# untitled.net
KiCad netlist of a schematic drawn in EAGLE
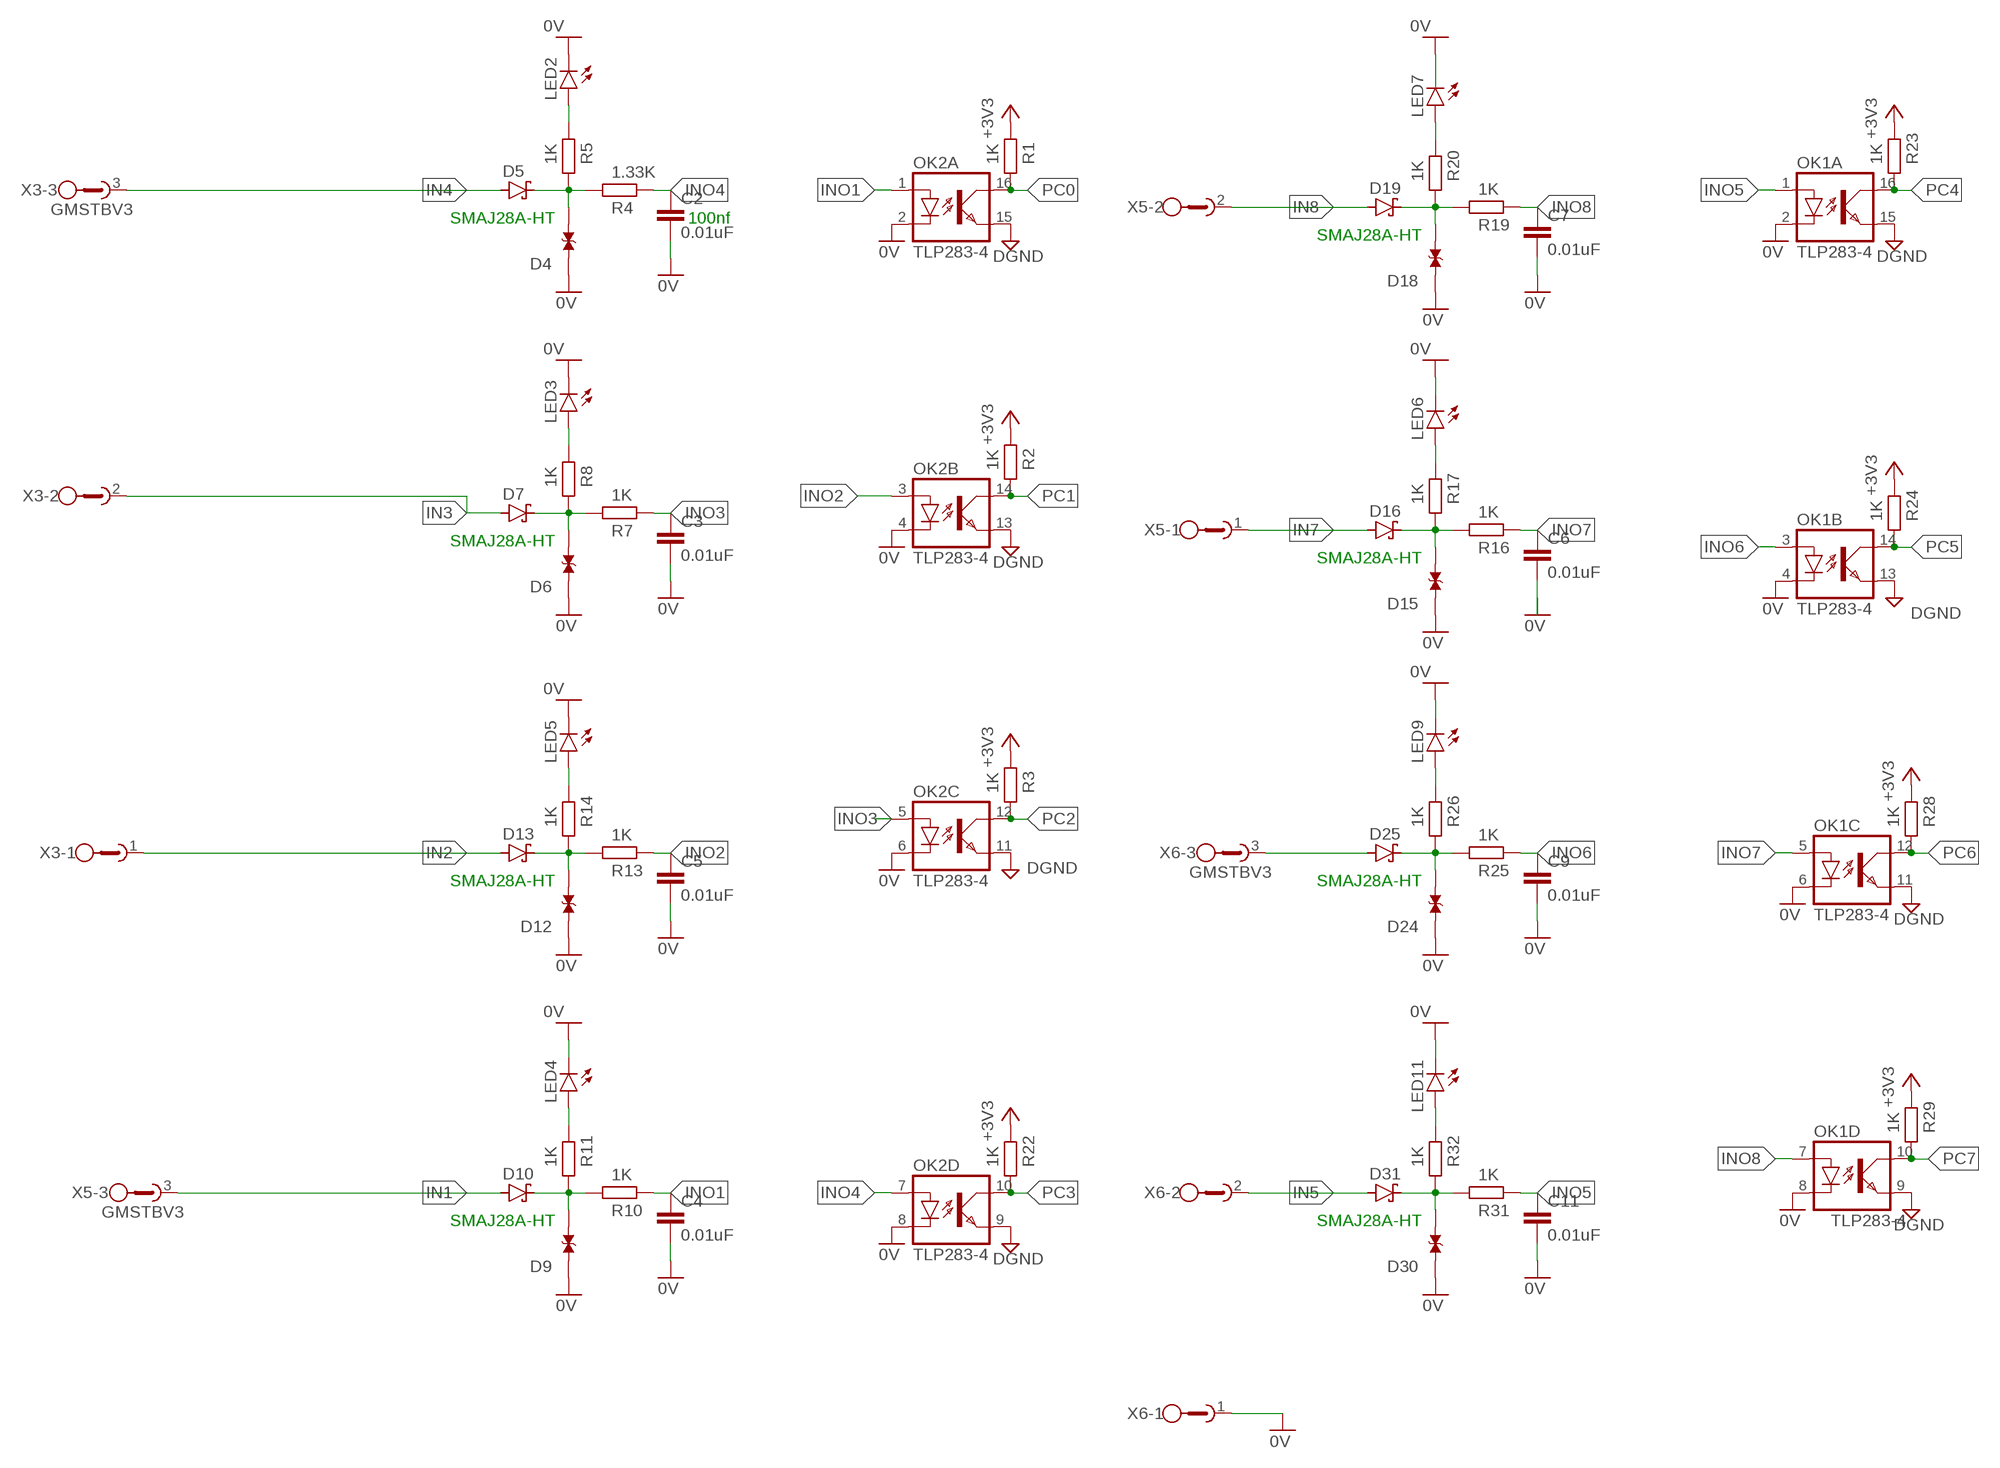
[diagram p0: schematic, sheet 1, part 1 of 2]
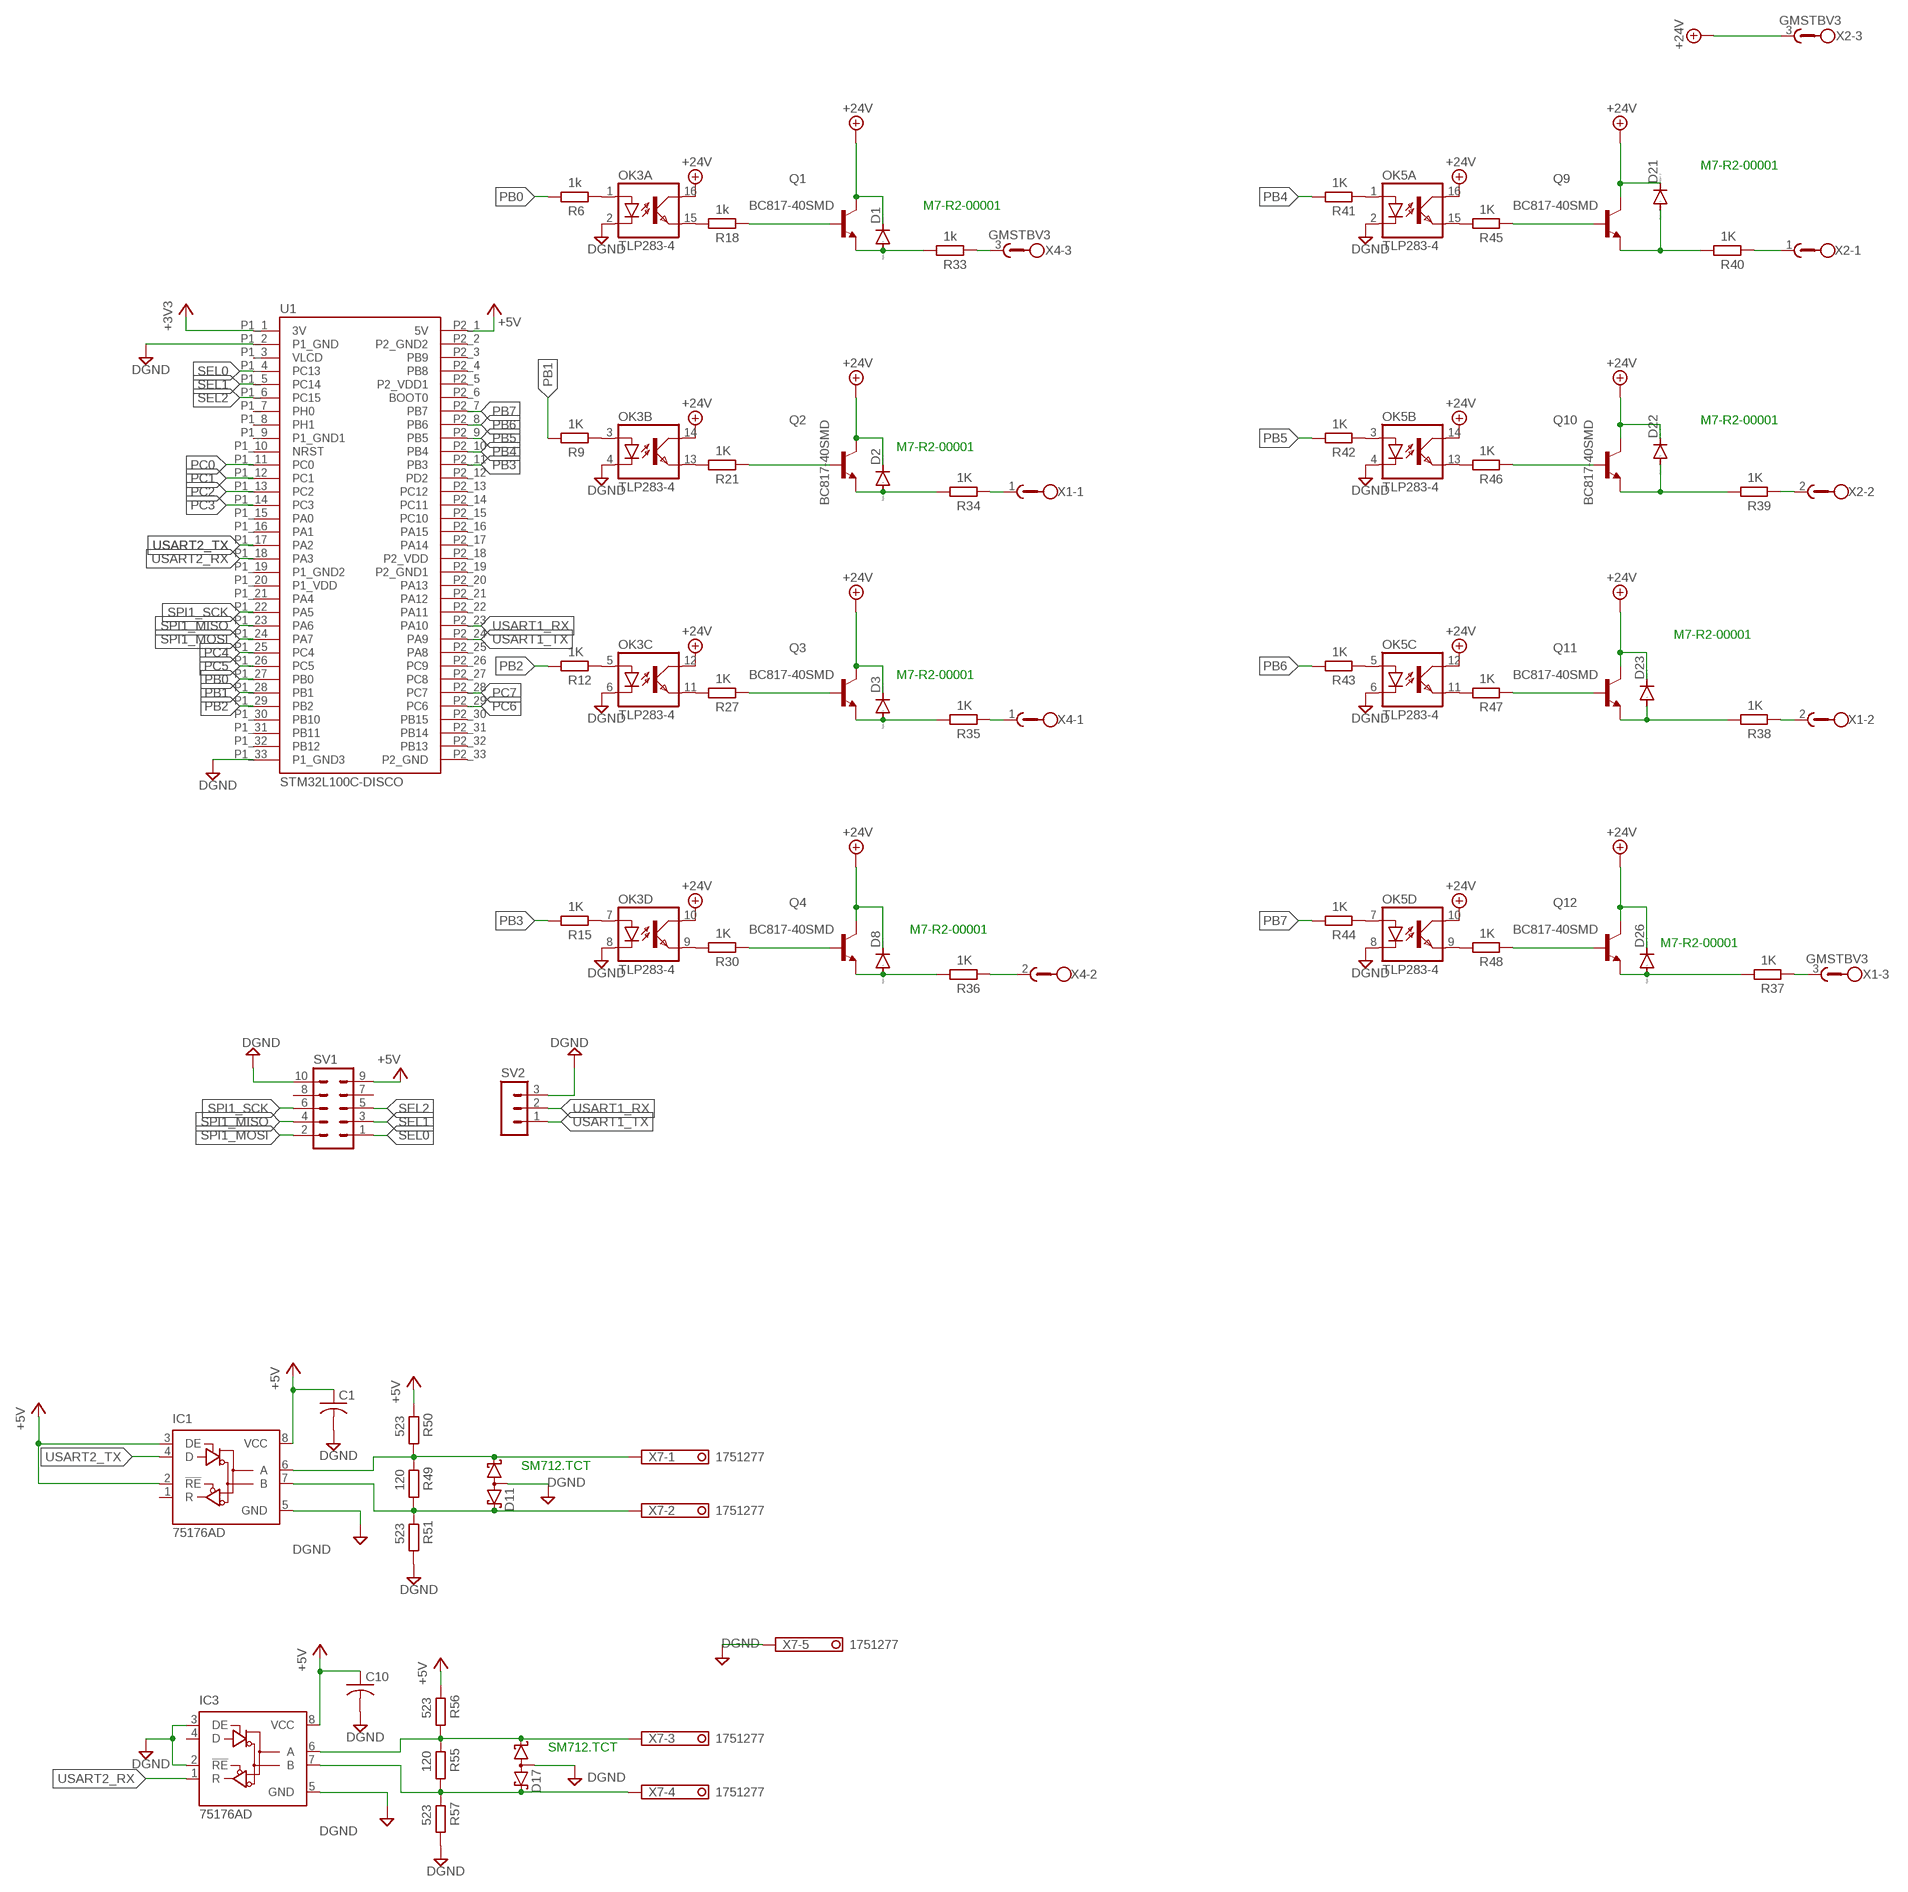
[diagram p1: schematic, sheet 1, part 2 of 2]

(export (version "E")
  (design (tool "Eeschema 10.0.6"))
  (components
    (comp (ref "C1")
      (value "C-USC0805")
      (footprint "eagle-import:C0805")
      (libsource (lib "eagle-import") (part "C-USC0805"))
    )
    (comp (ref "C2")
      (value "0.01uF")
      (footprint "eagle-import:C0805")
      (libsource (lib "eagle-import") (part "C-EUC0805"))
    )
    (comp (ref "C3")
      (value "0.01uF")
      (footprint "eagle-import:C0805")
      (libsource (lib "eagle-import") (part "C-EUC0805"))
    )
    (comp (ref "C4")
      (value "0.01uF")
      (footprint "eagle-import:C0805")
      (libsource (lib "eagle-import") (part "C-EUC0805"))
    )
    (comp (ref "C5")
      (value "0.01uF")
      (footprint "eagle-import:C0805")
      (libsource (lib "eagle-import") (part "C-EUC0805"))
    )
    (comp (ref "C6")
      (value "0.01uF")
      (footprint "eagle-import:C0805")
      (libsource (lib "eagle-import") (part "C-EUC0805"))
    )
    (comp (ref "C7")
      (value "0.01uF")
      (footprint "eagle-import:C0805")
      (libsource (lib "eagle-import") (part "C-EUC0805"))
    )
    (comp (ref "C9")
      (value "0.01uF")
      (footprint "eagle-import:C0805")
      (libsource (lib "eagle-import") (part "C-EUC0805"))
    )
    (comp (ref "C10")
      (value "C-USC0805")
      (footprint "eagle-import:C0805")
      (libsource (lib "eagle-import") (part "C-USC0805"))
    )
    (comp (ref "C11")
      (value "0.01uF")
      (footprint "eagle-import:C0805")
      (libsource (lib "eagle-import") (part "C-EUC0805"))
    )
    (comp (ref "D1")
      (value "S1M")
      (footprint "eagle-import:SMA")
      (libsource (lib "eagle-import") (part "S1M"))
    )
    (comp (ref "D2")
      (value "S1M")
      (footprint "eagle-import:SMA")
      (libsource (lib "eagle-import") (part "S1M"))
    )
    (comp (ref "D3")
      (value "S1M")
      (footprint "eagle-import:SMA")
      (libsource (lib "eagle-import") (part "S1M"))
    )
    (comp (ref "D4")
      (value "SMAJ28CA")
      (footprint "eagle-import:DIOM4325X250N")
      (fields (field (name "MF") "Littelfuse"))
      (libsource (lib "eagle-import") (part "SMAJ28CA"))
    )
    (comp (ref "D5")
      (value "SCHOTTKY-DIODESMD")
      (footprint "eagle-import:SMB")
      (libsource (lib "eagle-import") (part "SCHOTTKY-DIODESMD"))
    )
    (comp (ref "D6")
      (value "SMAJ28CA")
      (footprint "eagle-import:DIOM4325X250N")
      (fields (field (name "MF") "Littelfuse"))
      (libsource (lib "eagle-import") (part "SMAJ28CA"))
    )
    (comp (ref "D7")
      (value "SCHOTTKY-DIODESMD")
      (footprint "eagle-import:SMB")
      (libsource (lib "eagle-import") (part "SCHOTTKY-DIODESMD"))
    )
    (comp (ref "D8")
      (value "S1M")
      (footprint "eagle-import:SMA")
      (libsource (lib "eagle-import") (part "S1M"))
    )
    (comp (ref "D9")
      (value "SMAJ28CA")
      (footprint "eagle-import:DIOM4325X250N")
      (fields (field (name "MF") "Littelfuse"))
      (libsource (lib "eagle-import") (part "SMAJ28CA"))
    )
    (comp (ref "D10")
      (value "SCHOTTKY-DIODESMD")
      (footprint "eagle-import:SMB")
      (libsource (lib "eagle-import") (part "SCHOTTKY-DIODESMD"))
    )
    (comp (ref "D11")
      (value "BAS40-06")
      (footprint "eagle-import:SOT23")
      (libsource (lib "eagle-import") (part "BAS40-06"))
    )
    (comp (ref "D12")
      (value "SMAJ28CA")
      (footprint "eagle-import:DIOM4325X250N")
      (fields (field (name "MF") "Littelfuse"))
      (libsource (lib "eagle-import") (part "SMAJ28CA"))
    )
    (comp (ref "D13")
      (value "SCHOTTKY-DIODESMD")
      (footprint "eagle-import:SMB")
      (libsource (lib "eagle-import") (part "SCHOTTKY-DIODESMD"))
    )
    (comp (ref "D15")
      (value "SMAJ28CA")
      (footprint "eagle-import:DIOM4325X250N")
      (fields (field (name "MF") "Littelfuse"))
      (libsource (lib "eagle-import") (part "SMAJ28CA"))
    )
    (comp (ref "D16")
      (value "SCHOTTKY-DIODESMD")
      (footprint "eagle-import:SMB")
      (libsource (lib "eagle-import") (part "SCHOTTKY-DIODESMD"))
    )
    (comp (ref "D17")
      (value "BAS40-06")
      (footprint "eagle-import:SOT23")
      (libsource (lib "eagle-import") (part "BAS40-06"))
    )
    (comp (ref "D18")
      (value "SMAJ28CA")
      (footprint "eagle-import:DIOM4325X250N")
      (fields (field (name "MF") "Littelfuse"))
      (libsource (lib "eagle-import") (part "SMAJ28CA"))
    )
    (comp (ref "D19")
      (value "SCHOTTKY-DIODESMD")
      (footprint "eagle-import:SMB")
      (libsource (lib "eagle-import") (part "SCHOTTKY-DIODESMD"))
    )
    (comp (ref "D21")
      (value "S1M")
      (footprint "eagle-import:SMA")
      (libsource (lib "eagle-import") (part "S1M"))
    )
    (comp (ref "D22")
      (value "S1M")
      (footprint "eagle-import:SMA")
      (libsource (lib "eagle-import") (part "S1M"))
    )
    (comp (ref "D23")
      (value "S1M")
      (footprint "eagle-import:SMA")
      (libsource (lib "eagle-import") (part "S1M"))
    )
    (comp (ref "D24")
      (value "SMAJ28CA")
      (footprint "eagle-import:DIOM4325X250N")
      (fields (field (name "MF") "Littelfuse"))
      (libsource (lib "eagle-import") (part "SMAJ28CA"))
    )
    (comp (ref "D25")
      (value "SCHOTTKY-DIODESMD")
      (footprint "eagle-import:SMB")
      (libsource (lib "eagle-import") (part "SCHOTTKY-DIODESMD"))
    )
    (comp (ref "D26")
      (value "S1M")
      (footprint "eagle-import:SMA")
      (libsource (lib "eagle-import") (part "S1M"))
    )
    (comp (ref "D30")
      (value "SMAJ28CA")
      (footprint "eagle-import:DIOM4325X250N")
      (fields (field (name "MF") "Littelfuse"))
      (libsource (lib "eagle-import") (part "SMAJ28CA"))
    )
    (comp (ref "D31")
      (value "SCHOTTKY-DIODESMD")
      (footprint "eagle-import:SMB")
      (libsource (lib "eagle-import") (part "SCHOTTKY-DIODESMD"))
    )
    (comp (ref "IC1")
      (value "75176AD")
      (footprint "eagle-import:D_R-PDSO-G8")
      (libsource (lib "eagle-import") (part "75176AD"))
    )
    (comp (ref "IC3")
      (value "75176AD")
      (footprint "eagle-import:D_R-PDSO-G8")
      (libsource (lib "eagle-import") (part "75176AD"))
    )
    (comp (ref "LED2")
      (value "LEDCHIP-LED0805")
      (footprint "eagle-import:CHIP-LED0805")
      (libsource (lib "eagle-import") (part "LEDCHIP-LED0805"))
    )
    (comp (ref "LED3")
      (value "LEDCHIP-LED0805")
      (footprint "eagle-import:CHIP-LED0805")
      (libsource (lib "eagle-import") (part "LEDCHIP-LED0805"))
    )
    (comp (ref "LED4")
      (value "LEDCHIP-LED0805")
      (footprint "eagle-import:CHIP-LED0805")
      (libsource (lib "eagle-import") (part "LEDCHIP-LED0805"))
    )
    (comp (ref "LED5")
      (value "LEDCHIP-LED0805")
      (footprint "eagle-import:CHIP-LED0805")
      (libsource (lib "eagle-import") (part "LEDCHIP-LED0805"))
    )
    (comp (ref "LED6")
      (value "LEDCHIP-LED0805")
      (footprint "eagle-import:CHIP-LED0805")
      (libsource (lib "eagle-import") (part "LEDCHIP-LED0805"))
    )
    (comp (ref "LED7")
      (value "LEDCHIP-LED0805")
      (footprint "eagle-import:CHIP-LED0805")
      (libsource (lib "eagle-import") (part "LEDCHIP-LED0805"))
    )
    (comp (ref "LED9")
      (value "LEDCHIP-LED0805")
      (footprint "eagle-import:CHIP-LED0805")
      (libsource (lib "eagle-import") (part "LEDCHIP-LED0805"))
    )
    (comp (ref "LED11")
      (value "LEDCHIP-LED0805")
      (footprint "eagle-import:CHIP-LED0805")
      (libsource (lib "eagle-import") (part "LEDCHIP-LED0805"))
    )
    (comp (ref "OK1")
      (value "TLP283-4")
      (footprint "eagle-import:MINI-FLAT-16")
      (libsource (lib "eagle-import") (part "TLP283-4"))
    )
    (comp (ref "OK2")
      (value "TLP283-4")
      (footprint "eagle-import:MINI-FLAT-16")
      (libsource (lib "eagle-import") (part "TLP283-4"))
    )
    (comp (ref "OK3")
      (value "TLP283-4")
      (footprint "eagle-import:MINI-FLAT-16")
      (libsource (lib "eagle-import") (part "TLP283-4"))
    )
    (comp (ref "OK5")
      (value "TLP283-4")
      (footprint "eagle-import:MINI-FLAT-16")
      (libsource (lib "eagle-import") (part "TLP283-4"))
    )
    (comp (ref "Q1")
      (value "BC817-40SMD")
      (footprint "eagle-import:SOT23-BEC")
      (libsource (lib "eagle-import") (part "BC817SMD-40"))
    )
    (comp (ref "Q2")
      (value "BC817-40SMD")
      (footprint "eagle-import:SOT23-BEC")
      (libsource (lib "eagle-import") (part "BC817SMD-40"))
    )
    (comp (ref "Q3")
      (value "BC817-40SMD")
      (footprint "eagle-import:SOT23-BEC")
      (libsource (lib "eagle-import") (part "BC817SMD-40"))
    )
    (comp (ref "Q4")
      (value "BC817-40SMD")
      (footprint "eagle-import:SOT23-BEC")
      (libsource (lib "eagle-import") (part "BC817SMD-40"))
    )
    (comp (ref "Q9")
      (value "BC817-40SMD")
      (footprint "eagle-import:SOT23-BEC")
      (libsource (lib "eagle-import") (part "BC817SMD-40"))
    )
    (comp (ref "Q10")
      (value "BC817-40SMD")
      (footprint "eagle-import:SOT23-BEC")
      (libsource (lib "eagle-import") (part "BC817SMD-40"))
    )
    (comp (ref "Q11")
      (value "BC817-40SMD")
      (footprint "eagle-import:SOT23-BEC")
      (libsource (lib "eagle-import") (part "BC817SMD-40"))
    )
    (comp (ref "Q12")
      (value "BC817-40SMD")
      (footprint "eagle-import:SOT23-BEC")
      (libsource (lib "eagle-import") (part "BC817SMD-40"))
    )
    (comp (ref "R1")
      (value "1K")
      (footprint "eagle-import:R0805")
      (libsource (lib "eagle-import") (part "R-EU_R0805"))
    )
    (comp (ref "R2")
      (value "1K")
      (footprint "eagle-import:R0805")
      (libsource (lib "eagle-import") (part "R-EU_R0805"))
    )
    (comp (ref "R3")
      (value "1K")
      (footprint "eagle-import:R0805")
      (libsource (lib "eagle-import") (part "R-EU_R0805"))
    )
    (comp (ref "R4")
      (value "1.33K")
      (footprint "eagle-import:R0805")
      (libsource (lib "eagle-import") (part "R-EU_R0805"))
    )
    (comp (ref "R5")
      (value "1K")
      (footprint "eagle-import:R0805")
      (libsource (lib "eagle-import") (part "R-EU_R0805"))
    )
    (comp (ref "R6")
      (value "1k")
      (footprint "eagle-import:R0805")
      (libsource (lib "eagle-import") (part "R-EU_R0805"))
    )
    (comp (ref "R7")
      (value "1K")
      (footprint "eagle-import:R0805")
      (libsource (lib "eagle-import") (part "R-EU_R0805"))
    )
    (comp (ref "R8")
      (value "1K")
      (footprint "eagle-import:R0805")
      (libsource (lib "eagle-import") (part "R-EU_R0805"))
    )
    (comp (ref "R9")
      (value "1K")
      (footprint "eagle-import:R0805")
      (libsource (lib "eagle-import") (part "R-EU_R0805"))
    )
    (comp (ref "R10")
      (value "1K")
      (footprint "eagle-import:R0805")
      (libsource (lib "eagle-import") (part "R-EU_R0805"))
    )
    (comp (ref "R11")
      (value "1K")
      (footprint "eagle-import:R0805")
      (libsource (lib "eagle-import") (part "R-EU_R0805"))
    )
    (comp (ref "R12")
      (value "1K")
      (footprint "eagle-import:R0805")
      (libsource (lib "eagle-import") (part "R-EU_R0805"))
    )
    (comp (ref "R13")
      (value "1K")
      (footprint "eagle-import:R0805")
      (libsource (lib "eagle-import") (part "R-EU_R0805"))
    )
    (comp (ref "R14")
      (value "1K")
      (footprint "eagle-import:R0805")
      (libsource (lib "eagle-import") (part "R-EU_R0805"))
    )
    (comp (ref "R15")
      (value "1K")
      (footprint "eagle-import:R0805")
      (libsource (lib "eagle-import") (part "R-EU_R0805"))
    )
    (comp (ref "R16")
      (value "1K")
      (footprint "eagle-import:R0805")
      (libsource (lib "eagle-import") (part "R-EU_R0805"))
    )
    (comp (ref "R17")
      (value "1K")
      (footprint "eagle-import:R0805")
      (libsource (lib "eagle-import") (part "R-EU_R0805"))
    )
    (comp (ref "R18")
      (value "1k")
      (footprint "eagle-import:R0805")
      (libsource (lib "eagle-import") (part "R-EU_R0805"))
    )
    (comp (ref "R19")
      (value "1K")
      (footprint "eagle-import:R0805")
      (libsource (lib "eagle-import") (part "R-EU_R0805"))
    )
    (comp (ref "R20")
      (value "1K")
      (footprint "eagle-import:R0805")
      (libsource (lib "eagle-import") (part "R-EU_R0805"))
    )
    (comp (ref "R21")
      (value "1K")
      (footprint "eagle-import:R0805")
      (libsource (lib "eagle-import") (part "R-EU_R0805"))
    )
    (comp (ref "R22")
      (value "1K")
      (footprint "eagle-import:R0805")
      (libsource (lib "eagle-import") (part "R-EU_R0805"))
    )
    (comp (ref "R23")
      (value "1K")
      (footprint "eagle-import:R0805")
      (libsource (lib "eagle-import") (part "R-EU_R0805"))
    )
    (comp (ref "R24")
      (value "1K")
      (footprint "eagle-import:R0805")
      (libsource (lib "eagle-import") (part "R-EU_R0805"))
    )
    (comp (ref "R25")
      (value "1K")
      (footprint "eagle-import:R0805")
      (libsource (lib "eagle-import") (part "R-EU_R0805"))
    )
    (comp (ref "R26")
      (value "1K")
      (footprint "eagle-import:R0805")
      (libsource (lib "eagle-import") (part "R-EU_R0805"))
    )
    (comp (ref "R27")
      (value "1K")
      (footprint "eagle-import:R0805")
      (libsource (lib "eagle-import") (part "R-EU_R0805"))
    )
    (comp (ref "R28")
      (value "1K")
      (footprint "eagle-import:R0805")
      (libsource (lib "eagle-import") (part "R-EU_R0805"))
    )
    (comp (ref "R29")
      (value "1K")
      (footprint "eagle-import:R0805")
      (libsource (lib "eagle-import") (part "R-EU_R0805"))
    )
    (comp (ref "R30")
      (value "1K")
      (footprint "eagle-import:R0805")
      (libsource (lib "eagle-import") (part "R-EU_R0805"))
    )
    (comp (ref "R31")
      (value "1K")
      (footprint "eagle-import:R0805")
      (libsource (lib "eagle-import") (part "R-EU_R0805"))
    )
    (comp (ref "R32")
      (value "1K")
      (footprint "eagle-import:R0805")
      (libsource (lib "eagle-import") (part "R-EU_R0805"))
    )
    (comp (ref "R33")
      (value "1k")
      (footprint "eagle-import:R0805")
      (libsource (lib "eagle-import") (part "R-EU_R0805"))
    )
    (comp (ref "R34")
      (value "1K")
      (footprint "eagle-import:R0805")
      (libsource (lib "eagle-import") (part "R-EU_R0805"))
    )
    (comp (ref "R35")
      (value "1K")
      (footprint "eagle-import:R0805")
      (libsource (lib "eagle-import") (part "R-EU_R0805"))
    )
    (comp (ref "R36")
      (value "1K")
      (footprint "eagle-import:R0805")
      (libsource (lib "eagle-import") (part "R-EU_R0805"))
    )
    (comp (ref "R37")
      (value "1K")
      (footprint "eagle-import:R0805")
      (libsource (lib "eagle-import") (part "R-EU_R0805"))
    )
    (comp (ref "R38")
      (value "1K")
      (footprint "eagle-import:R0805")
      (libsource (lib "eagle-import") (part "R-EU_R0805"))
    )
    (comp (ref "R39")
      (value "1K")
      (footprint "eagle-import:R0805")
      (libsource (lib "eagle-import") (part "R-EU_R0805"))
    )
    (comp (ref "R40")
      (value "1K")
      (footprint "eagle-import:R0805")
      (libsource (lib "eagle-import") (part "R-EU_R0805"))
    )
    (comp (ref "R41")
      (value "1K")
      (footprint "eagle-import:R0805")
      (libsource (lib "eagle-import") (part "R-EU_R0805"))
    )
    (comp (ref "R42")
      (value "1K")
      (footprint "eagle-import:R0805")
      (libsource (lib "eagle-import") (part "R-EU_R0805"))
    )
    (comp (ref "R43")
      (value "1K")
      (footprint "eagle-import:R0805")
      (libsource (lib "eagle-import") (part "R-EU_R0805"))
    )
    (comp (ref "R44")
      (value "1K")
      (footprint "eagle-import:R0805")
      (libsource (lib "eagle-import") (part "R-EU_R0805"))
    )
    (comp (ref "R45")
      (value "1K")
      (footprint "eagle-import:R0805")
      (libsource (lib "eagle-import") (part "R-EU_R0805"))
    )
    (comp (ref "R46")
      (value "1K")
      (footprint "eagle-import:R0805")
      (libsource (lib "eagle-import") (part "R-EU_R0805"))
    )
    (comp (ref "R47")
      (value "1K")
      (footprint "eagle-import:R0805")
      (libsource (lib "eagle-import") (part "R-EU_R0805"))
    )
    (comp (ref "R48")
      (value "1K")
      (footprint "eagle-import:R0805")
      (libsource (lib "eagle-import") (part "R-EU_R0805"))
    )
    (comp (ref "R49")
      (value "120")
      (footprint "eagle-import:R0805")
      (libsource (lib "eagle-import") (part "R-EU_R0805"))
    )
    (comp (ref "R50")
      (value "523")
      (footprint "eagle-import:R0805")
      (libsource (lib "eagle-import") (part "R-EU_R0805"))
    )
    (comp (ref "R51")
      (value "523")
      (footprint "eagle-import:R0805")
      (libsource (lib "eagle-import") (part "R-EU_R0805"))
    )
    (comp (ref "R55")
      (value "120")
      (footprint "eagle-import:R0805")
      (libsource (lib "eagle-import") (part "R-EU_R0805"))
    )
    (comp (ref "R56")
      (value "523")
      (footprint "eagle-import:R0805")
      (libsource (lib "eagle-import") (part "R-EU_R0805"))
    )
    (comp (ref "R57")
      (value "523")
      (footprint "eagle-import:R0805")
      (libsource (lib "eagle-import") (part "R-EU_R0805"))
    )
    (comp (ref "SV1")
      (value "MA05-2")
      (footprint "eagle-import:MA05-2")
      (libsource (lib "eagle-import") (part "MA05-2"))
    )
    (comp (ref "SV2")
      (value "MA03-1")
      (footprint "eagle-import:MA03-1")
      (libsource (lib "eagle-import") (part "MA03-1"))
    )
    (comp (ref "U1")
      (value "STM32L100C-DISCO")
      (footprint "eagle-import:DEV_STM32L100C-DISCO")
      (fields (field (name "MF") "STMicroelectronics"))
      (libsource (lib "eagle-import") (part "STM32L100C-DISCO"))
    )
    (comp (ref "X1")
      (value "GMSTBV3")
      (footprint "eagle-import:GMSTBV3")
      (fields (field (name "MPN") "GMSTBVA2,5/3-G-7,62"))
      (libsource (lib "eagle-import") (part "GMSTBV3"))
    )
    (comp (ref "X2")
      (value "GMSTBV3")
      (footprint "eagle-import:GMSTBV3")
      (fields (field (name "MPN") "GMSTBVA2,5/3-G-7,62"))
      (libsource (lib "eagle-import") (part "GMSTBV3"))
    )
    (comp (ref "X3")
      (value "GMSTBV3")
      (footprint "eagle-import:GMSTBV3")
      (fields (field (name "MPN") "GMSTBVA2,5/3-G-7,62"))
      (libsource (lib "eagle-import") (part "GMSTBV3"))
    )
    (comp (ref "X4")
      (value "GMSTBV3")
      (footprint "eagle-import:GMSTBV3")
      (fields (field (name "MPN") "GMSTBVA2,5/3-G-7,62"))
      (libsource (lib "eagle-import") (part "GMSTBV3"))
    )
    (comp (ref "X5")
      (value "GMSTBV3")
      (footprint "eagle-import:GMSTBV3")
      (fields (field (name "MPN") "GMSTBVA2,5/3-G-7,62"))
      (libsource (lib "eagle-import") (part "GMSTBV3"))
    )
    (comp (ref "X6")
      (value "GMSTBV3")
      (footprint "eagle-import:GMSTBV3")
      (fields (field (name "MPN") "GMSTBVA2,5/3-G-7,62"))
      (libsource (lib "eagle-import") (part "GMSTBV3"))
    )
    (comp (ref "X7")
      (value "1751277")
      (footprint "eagle-import:1751277")
      (libsource (lib "eagle-import") (part "1751277"))
    )
  )
  (nets
    (net (code "1") (name "+3V3") (class "Default")
      (node (ref "R1") (pin "2") (pinfunction "2_2") (pintype "passive"))
      (node (ref "R2") (pin "2") (pinfunction "2_2") (pintype "passive"))
      (node (ref "R22") (pin "2") (pinfunction "2_2") (pintype "passive"))
      (node (ref "R23") (pin "2") (pinfunction "2_2") (pintype "passive"))
      (node (ref "R24") (pin "2") (pinfunction "2_2") (pintype "passive"))
      (node (ref "R28") (pin "2") (pinfunction "2_2") (pintype "passive"))
      (node (ref "R29") (pin "2") (pinfunction "2_2") (pintype "passive"))
      (node (ref "R3") (pin "2") (pinfunction "2_2") (pintype "passive"))
      (node (ref "U1") (pin "P1_1") (pinfunction "3V_P1_1") (pintype "power_in"))
    )
    (net (code "2") (name "+5V") (class "Default")
      (node (ref "C1") (pin "1") (pinfunction "1_1") (pintype "passive"))
      (node (ref "C10") (pin "1") (pinfunction "1_1") (pintype "passive"))
      (node (ref "IC1") (pin "2") (pinfunction "~{RE}_2") (pintype "input"))
      (node (ref "IC1") (pin "3") (pinfunction "DE_3") (pintype "input"))
      (node (ref "IC1") (pin "8") (pinfunction "VCC_8") (pintype "power_in"))
      (node (ref "IC3") (pin "8") (pinfunction "VCC_8") (pintype "power_in"))
      (node (ref "R50") (pin "2") (pinfunction "2_2") (pintype "passive"))
      (node (ref "R56") (pin "2") (pinfunction "2_2") (pintype "passive"))
      (node (ref "SV1") (pin "9") (pinfunction "9_9") (pintype "passive"))
      (node (ref "U1") (pin "P2_1") (pinfunction "5V_P2_1") (pintype "power_in"))
    )
    (net (code "3") (name "+24V") (class "Default")
      (node (ref "D1") (pin "C") (pinfunction "C_C") (pintype "passive"))
      (node (ref "D2") (pin "C") (pinfunction "C_C") (pintype "passive"))
      (node (ref "D21") (pin "C") (pinfunction "C_C") (pintype "passive"))
      (node (ref "D22") (pin "C") (pinfunction "C_C") (pintype "passive"))
      (node (ref "D23") (pin "C") (pinfunction "C_C") (pintype "passive"))
      (node (ref "D26") (pin "C") (pinfunction "C_C") (pintype "passive"))
      (node (ref "D3") (pin "C") (pinfunction "C_C") (pintype "passive"))
      (node (ref "D8") (pin "C") (pinfunction "C_C") (pintype "passive"))
      (node (ref "OK3") (pin "10") (pinfunction "COL_10") (pintype "passive"))
      (node (ref "OK3") (pin "12") (pinfunction "COL_12") (pintype "passive"))
      (node (ref "OK3") (pin "14") (pinfunction "COL_14") (pintype "passive"))
      (node (ref "OK3") (pin "16") (pinfunction "COL_16") (pintype "passive"))
      (node (ref "OK5") (pin "10") (pinfunction "COL_10") (pintype "passive"))
      (node (ref "OK5") (pin "12") (pinfunction "COL_12") (pintype "passive"))
      (node (ref "OK5") (pin "14") (pinfunction "COL_14") (pintype "passive"))
      (node (ref "OK5") (pin "16") (pinfunction "COL_16") (pintype "passive"))
      (node (ref "Q1") (pin "C") (pinfunction "C_C") (pintype "passive"))
      (node (ref "Q10") (pin "C") (pinfunction "C_C") (pintype "passive"))
      (node (ref "Q11") (pin "C") (pinfunction "C_C") (pintype "passive"))
      (node (ref "Q12") (pin "C") (pinfunction "C_C") (pintype "passive"))
      (node (ref "Q2") (pin "C") (pinfunction "C_C") (pintype "passive"))
      (node (ref "Q3") (pin "C") (pinfunction "C_C") (pintype "passive"))
      (node (ref "Q4") (pin "C") (pinfunction "C_C") (pintype "passive"))
      (node (ref "Q9") (pin "C") (pinfunction "C_C") (pintype "passive"))
      (node (ref "X2") (pin "3") (pinfunction "1_3") (pintype "passive"))
    )
    (net (code "4") (name "/P1_GND1") (class "Default")
      (node (ref "U1") (pin "P1_9") (pinfunction "P1_GND1_P1_9") (pintype "power_in"))
    )
    (net (code "5") (name "/P1_GND2") (class "Default")
      (node (ref "U1") (pin "P1_19") (pinfunction "P1_GND2_P1_19") (pintype "power_in"))
    )
    (net (code "6") (name "/P1_VDD") (class "Default")
      (node (ref "U1") (pin "P1_20") (pinfunction "P1_VDD_P1_20") (pintype "power_in"))
    )
    (net (code "7") (name "/P2_GND") (class "Default")
      (node (ref "U1") (pin "P2_33") (pinfunction "P2_GND_P2_33") (pintype "power_in"))
    )
    (net (code "8") (name "/P2_GND1") (class "Default")
      (node (ref "U1") (pin "P2_19") (pinfunction "P2_GND1_P2_19") (pintype "power_in"))
    )
    (net (code "9") (name "/P2_GND2") (class "Default")
      (node (ref "U1") (pin "P2_2") (pinfunction "P2_GND2_P2_2") (pintype "power_in"))
    )
    (net (code "10") (name "/P2_VDD") (class "Default")
      (node (ref "U1") (pin "P2_18") (pinfunction "P2_VDD_P2_18") (pintype "power_in"))
    )
    (net (code "11") (name "/P2_VDD1") (class "Default")
      (node (ref "U1") (pin "P2_5") (pinfunction "P2_VDD1_P2_5") (pintype "power_in"))
    )
    (net (code "12") (name "/VLCD") (class "Default")
      (node (ref "U1") (pin "P1_3") (pinfunction "VLCD_P1_3") (pintype "power_in"))
    )
    (net (code "13") (name "0V") (class "Default")
      (node (ref "C11") (pin "2") (pinfunction "2_2") (pintype "passive"))
      (node (ref "C2") (pin "2") (pinfunction "2_2") (pintype "passive"))
      (node (ref "C3") (pin "2") (pinfunction "2_2") (pintype "passive"))
      (node (ref "C4") (pin "2") (pinfunction "2_2") (pintype "passive"))
      (node (ref "C5") (pin "2") (pinfunction "2_2") (pintype "passive"))
      (node (ref "C6") (pin "2") (pinfunction "2_2") (pintype "passive"))
      (node (ref "C7") (pin "2") (pinfunction "2_2") (pintype "passive"))
      (node (ref "C9") (pin "2") (pinfunction "2_2") (pintype "passive"))
      (node (ref "D12") (pin "1") (pinfunction "1_1") (pintype "passive"))
      (node (ref "D15") (pin "1") (pinfunction "1_1") (pintype "passive"))
      (node (ref "D18") (pin "1") (pinfunction "1_1") (pintype "passive"))
      (node (ref "D24") (pin "1") (pinfunction "1_1") (pintype "passive"))
      (node (ref "D30") (pin "1") (pinfunction "1_1") (pintype "passive"))
      (node (ref "D4") (pin "1") (pinfunction "1_1") (pintype "passive"))
      (node (ref "D6") (pin "1") (pinfunction "1_1") (pintype "passive"))
      (node (ref "D9") (pin "1") (pinfunction "1_1") (pintype "passive"))
      (node (ref "LED11") (pin "C") (pinfunction "C_C") (pintype "passive"))
      (node (ref "LED2") (pin "C") (pinfunction "C_C") (pintype "passive"))
      (node (ref "LED3") (pin "C") (pinfunction "C_C") (pintype "passive"))
      (node (ref "LED4") (pin "C") (pinfunction "C_C") (pintype "passive"))
      (node (ref "LED5") (pin "C") (pinfunction "C_C") (pintype "passive"))
      (node (ref "LED6") (pin "C") (pinfunction "C_C") (pintype "passive"))
      (node (ref "LED7") (pin "C") (pinfunction "C_C") (pintype "passive"))
      (node (ref "LED9") (pin "C") (pinfunction "C_C") (pintype "passive"))
      (node (ref "OK1") (pin "2") (pinfunction "C_2") (pintype "passive"))
      (node (ref "OK1") (pin "4") (pinfunction "C_4") (pintype "passive"))
      (node (ref "OK1") (pin "6") (pinfunction "C_6") (pintype "passive"))
      (node (ref "OK1") (pin "8") (pinfunction "C_8") (pintype "passive"))
      (node (ref "OK2") (pin "2") (pinfunction "C_2") (pintype "passive"))
      (node (ref "OK2") (pin "4") (pinfunction "C_4") (pintype "passive"))
      (node (ref "OK2") (pin "6") (pinfunction "C_6") (pintype "passive"))
      (node (ref "OK2") (pin "8") (pinfunction "C_8") (pintype "passive"))
      (node (ref "X6") (pin "1") (pinfunction "1_1") (pintype "passive"))
    )
    (net (code "14") (name "DGND") (class "Default")
      (node (ref "C1") (pin "2") (pinfunction "2_2") (pintype "passive"))
      (node (ref "C10") (pin "2") (pinfunction "2_2") (pintype "passive"))
      (node (ref "D11") (pin "3") (pinfunction "AA_3") (pintype "passive"))
      (node (ref "D17") (pin "3") (pinfunction "AA_3") (pintype "passive"))
      (node (ref "IC1") (pin "5") (pinfunction "GND_5") (pintype "power_in"))
      (node (ref "IC3") (pin "2") (pinfunction "~{RE}_2") (pintype "input"))
      (node (ref "IC3") (pin "3") (pinfunction "DE_3") (pintype "input"))
      (node (ref "IC3") (pin "5") (pinfunction "GND_5") (pintype "power_in"))
      (node (ref "OK1") (pin "11") (pinfunction "EMIT_11") (pintype "passive"))
      (node (ref "OK1") (pin "13") (pinfunction "EMIT_13") (pintype "passive"))
      (node (ref "OK1") (pin "15") (pinfunction "EMIT_15") (pintype "passive"))
      (node (ref "OK1") (pin "9") (pinfunction "EMIT_9") (pintype "passive"))
      (node (ref "OK2") (pin "11") (pinfunction "EMIT_11") (pintype "passive"))
      (node (ref "OK2") (pin "13") (pinfunction "EMIT_13") (pintype "passive"))
      (node (ref "OK2") (pin "15") (pinfunction "EMIT_15") (pintype "passive"))
      (node (ref "OK2") (pin "9") (pinfunction "EMIT_9") (pintype "passive"))
      (node (ref "OK3") (pin "2") (pinfunction "C_2") (pintype "passive"))
      (node (ref "OK3") (pin "4") (pinfunction "C_4") (pintype "passive"))
      (node (ref "OK3") (pin "6") (pinfunction "C_6") (pintype "passive"))
      (node (ref "OK3") (pin "8") (pinfunction "C_8") (pintype "passive"))
      (node (ref "OK5") (pin "2") (pinfunction "C_2") (pintype "passive"))
      (node (ref "OK5") (pin "4") (pinfunction "C_4") (pintype "passive"))
      (node (ref "OK5") (pin "6") (pinfunction "C_6") (pintype "passive"))
      (node (ref "OK5") (pin "8") (pinfunction "C_8") (pintype "passive"))
      (node (ref "R51") (pin "1") (pinfunction "1_1") (pintype "passive"))
      (node (ref "R57") (pin "1") (pinfunction "1_1") (pintype "passive"))
      (node (ref "SV1") (pin "10") (pinfunction "10_10") (pintype "passive"))
      (node (ref "SV2") (pin "3") (pinfunction "3_3") (pintype "passive"))
      (node (ref "U1") (pin "P1_2") (pinfunction "P1_GND_P1_2") (pintype "power_in"))
      (node (ref "U1") (pin "P1_33") (pinfunction "P1_GND3_P1_33") (pintype "power_in"))
      (node (ref "X7") (pin "5") (pinfunction "K_5") (pintype "passive"))
    )
    (net (code "15") (name "IN1") (class "Default")
      (node (ref "D10") (pin "A") (pinfunction "A_A") (pintype "passive"))
      (node (ref "X5") (pin "3") (pinfunction "1_3") (pintype "passive"))
    )
    (net (code "16") (name "IN2") (class "Default")
      (node (ref "D13") (pin "A") (pinfunction "A_A") (pintype "passive"))
      (node (ref "X3") (pin "1") (pinfunction "1_1") (pintype "passive"))
    )
    (net (code "17") (name "IN3") (class "Default")
      (node (ref "D7") (pin "A") (pinfunction "A_A") (pintype "passive"))
      (node (ref "X3") (pin "2") (pinfunction "1_2") (pintype "passive"))
    )
    (net (code "18") (name "IN4") (class "Default")
      (node (ref "D5") (pin "A") (pinfunction "A_A") (pintype "passive"))
      (node (ref "X3") (pin "3") (pinfunction "1_3") (pintype "passive"))
    )
    (net (code "19") (name "IN5") (class "Default")
      (node (ref "D31") (pin "A") (pinfunction "A_A") (pintype "passive"))
      (node (ref "X6") (pin "2") (pinfunction "1_2") (pintype "passive"))
    )
    (net (code "20") (name "IN7") (class "Default")
      (node (ref "D16") (pin "A") (pinfunction "A_A") (pintype "passive"))
      (node (ref "X5") (pin "1") (pinfunction "1_1") (pintype "passive"))
    )
    (net (code "21") (name "IN8") (class "Default")
      (node (ref "D19") (pin "A") (pinfunction "A_A") (pintype "passive"))
      (node (ref "X5") (pin "2") (pinfunction "1_2") (pintype "passive"))
    )
    (net (code "22") (name "INO1") (class "Default")
      (node (ref "C4") (pin "1") (pinfunction "1_1") (pintype "passive"))
      (node (ref "OK2") (pin "1") (pinfunction "A_1") (pintype "passive"))
      (node (ref "R10") (pin "2") (pinfunction "2_2") (pintype "passive"))
    )
    (net (code "23") (name "INO2") (class "Default")
      (node (ref "C5") (pin "1") (pinfunction "1_1") (pintype "passive"))
      (node (ref "OK2") (pin "3") (pinfunction "A_3") (pintype "passive"))
      (node (ref "R13") (pin "2") (pinfunction "2_2") (pintype "passive"))
    )
    (net (code "24") (name "INO3") (class "Default")
      (node (ref "C3") (pin "1") (pinfunction "1_1") (pintype "passive"))
      (node (ref "OK2") (pin "5") (pinfunction "A_5") (pintype "passive"))
      (node (ref "R7") (pin "2") (pinfunction "2_2") (pintype "passive"))
    )
    (net (code "25") (name "INO4") (class "Default")
      (node (ref "C2") (pin "1") (pinfunction "1_1") (pintype "passive"))
      (node (ref "OK2") (pin "7") (pinfunction "A_7") (pintype "passive"))
      (node (ref "R4") (pin "2") (pinfunction "2_2") (pintype "passive"))
    )
    (net (code "26") (name "INO5") (class "Default")
      (node (ref "C11") (pin "1") (pinfunction "1_1") (pintype "passive"))
      (node (ref "OK1") (pin "1") (pinfunction "A_1") (pintype "passive"))
      (node (ref "R31") (pin "2") (pinfunction "2_2") (pintype "passive"))
    )
    (net (code "27") (name "INO6") (class "Default")
      (node (ref "C9") (pin "1") (pinfunction "1_1") (pintype "passive"))
      (node (ref "OK1") (pin "3") (pinfunction "A_3") (pintype "passive"))
      (node (ref "R25") (pin "2") (pinfunction "2_2") (pintype "passive"))
    )
    (net (code "28") (name "INO7") (class "Default")
      (node (ref "C6") (pin "1") (pinfunction "1_1") (pintype "passive"))
      (node (ref "OK1") (pin "5") (pinfunction "A_5") (pintype "passive"))
      (node (ref "R16") (pin "2") (pinfunction "2_2") (pintype "passive"))
    )
    (net (code "29") (name "INO8") (class "Default")
      (node (ref "C7") (pin "1") (pinfunction "1_1") (pintype "passive"))
      (node (ref "OK1") (pin "7") (pinfunction "A_7") (pintype "passive"))
      (node (ref "R19") (pin "2") (pinfunction "2_2") (pintype "passive"))
    )
    (net (code "30") (name "Net-(D1-PadA)") (class "Default")
      (node (ref "D1") (pin "A") (pinfunction "A_A") (pintype "passive"))
      (node (ref "Q1") (pin "E") (pinfunction "E_E") (pintype "passive"))
      (node (ref "R33") (pin "1") (pinfunction "1_1") (pintype "passive"))
    )
    (net (code "31") (name "Net-(D2-PadA)") (class "Default")
      (node (ref "D2") (pin "A") (pinfunction "A_A") (pintype "passive"))
      (node (ref "Q2") (pin "E") (pinfunction "E_E") (pintype "passive"))
      (node (ref "R34") (pin "1") (pinfunction "1_1") (pintype "passive"))
    )
    (net (code "32") (name "Net-(D3-PadA)") (class "Default")
      (node (ref "D3") (pin "A") (pinfunction "A_A") (pintype "passive"))
      (node (ref "Q3") (pin "E") (pinfunction "E_E") (pintype "passive"))
      (node (ref "R35") (pin "1") (pinfunction "1_1") (pintype "passive"))
    )
    (net (code "33") (name "Net-(D4-Pad2)") (class "Default")
      (node (ref "D4") (pin "2") (pinfunction "2_2") (pintype "passive"))
      (node (ref "D5") (pin "C") (pinfunction "C_C") (pintype "passive"))
      (node (ref "R4") (pin "1") (pinfunction "1_1") (pintype "passive"))
      (node (ref "R5") (pin "1") (pinfunction "1_1") (pintype "passive"))
    )
    (net (code "34") (name "Net-(D6-Pad2)") (class "Default")
      (node (ref "D6") (pin "2") (pinfunction "2_2") (pintype "passive"))
      (node (ref "D7") (pin "C") (pinfunction "C_C") (pintype "passive"))
      (node (ref "R7") (pin "1") (pinfunction "1_1") (pintype "passive"))
      (node (ref "R8") (pin "1") (pinfunction "1_1") (pintype "passive"))
    )
    (net (code "35") (name "Net-(D8-PadA)") (class "Default")
      (node (ref "D8") (pin "A") (pinfunction "A_A") (pintype "passive"))
      (node (ref "Q4") (pin "E") (pinfunction "E_E") (pintype "passive"))
      (node (ref "R36") (pin "1") (pinfunction "1_1") (pintype "passive"))
    )
    (net (code "36") (name "Net-(D10-PadC)") (class "Default")
      (node (ref "D10") (pin "C") (pinfunction "C_C") (pintype "passive"))
      (node (ref "D9") (pin "2") (pinfunction "2_2") (pintype "passive"))
      (node (ref "R10") (pin "1") (pinfunction "1_1") (pintype "passive"))
      (node (ref "R11") (pin "1") (pinfunction "1_1") (pintype "passive"))
    )
    (net (code "37") (name "Net-(D11-K1)") (class "Default")
      (node (ref "D11") (pin "1") (pinfunction "K1_1") (pintype "passive"))
      (node (ref "IC1") (pin "6") (pinfunction "A_6") (pintype "output"))
      (node (ref "R49") (pin "2") (pinfunction "2_2") (pintype "passive"))
      (node (ref "R50") (pin "1") (pinfunction "1_1") (pintype "passive"))
      (node (ref "X7") (pin "1") (pinfunction "K_1") (pintype "passive"))
    )
    (net (code "38") (name "Net-(D11-K2)") (class "Default")
      (node (ref "D11") (pin "2") (pinfunction "K2_2") (pintype "passive"))
      (node (ref "IC1") (pin "7") (pinfunction "B_7") (pintype "output"))
      (node (ref "R49") (pin "1") (pinfunction "1_1") (pintype "passive"))
      (node (ref "R51") (pin "2") (pinfunction "2_2") (pintype "passive"))
      (node (ref "X7") (pin "2") (pinfunction "K_2") (pintype "passive"))
    )
    (net (code "39") (name "Net-(D12-Pad2)") (class "Default")
      (node (ref "D12") (pin "2") (pinfunction "2_2") (pintype "passive"))
      (node (ref "D13") (pin "C") (pinfunction "C_C") (pintype "passive"))
      (node (ref "R13") (pin "1") (pinfunction "1_1") (pintype "passive"))
      (node (ref "R14") (pin "1") (pinfunction "1_1") (pintype "passive"))
    )
    (net (code "40") (name "Net-(D15-Pad2)") (class "Default")
      (node (ref "D15") (pin "2") (pinfunction "2_2") (pintype "passive"))
      (node (ref "D16") (pin "C") (pinfunction "C_C") (pintype "passive"))
      (node (ref "R16") (pin "1") (pinfunction "1_1") (pintype "passive"))
      (node (ref "R17") (pin "1") (pinfunction "1_1") (pintype "passive"))
    )
    (net (code "41") (name "Net-(D17-K1)") (class "Default")
      (node (ref "D17") (pin "1") (pinfunction "K1_1") (pintype "passive"))
      (node (ref "IC3") (pin "6") (pinfunction "A_6") (pintype "output"))
      (node (ref "R55") (pin "2") (pinfunction "2_2") (pintype "passive"))
      (node (ref "R56") (pin "1") (pinfunction "1_1") (pintype "passive"))
      (node (ref "X7") (pin "3") (pinfunction "K_3") (pintype "passive"))
    )
    (net (code "42") (name "Net-(D17-K2)") (class "Default")
      (node (ref "D17") (pin "2") (pinfunction "K2_2") (pintype "passive"))
      (node (ref "IC3") (pin "7") (pinfunction "B_7") (pintype "output"))
      (node (ref "R55") (pin "1") (pinfunction "1_1") (pintype "passive"))
      (node (ref "R57") (pin "2") (pinfunction "2_2") (pintype "passive"))
      (node (ref "X7") (pin "4") (pinfunction "K_4") (pintype "passive"))
    )
    (net (code "43") (name "Net-(D18-Pad2)") (class "Default")
      (node (ref "D18") (pin "2") (pinfunction "2_2") (pintype "passive"))
      (node (ref "D19") (pin "C") (pinfunction "C_C") (pintype "passive"))
      (node (ref "R19") (pin "1") (pinfunction "1_1") (pintype "passive"))
      (node (ref "R20") (pin "1") (pinfunction "1_1") (pintype "passive"))
    )
    (net (code "44") (name "Net-(D21-PadA)") (class "Default")
      (node (ref "D21") (pin "A") (pinfunction "A_A") (pintype "passive"))
      (node (ref "Q9") (pin "E") (pinfunction "E_E") (pintype "passive"))
      (node (ref "R40") (pin "1") (pinfunction "1_1") (pintype "passive"))
    )
    (net (code "45") (name "Net-(D22-PadA)") (class "Default")
      (node (ref "D22") (pin "A") (pinfunction "A_A") (pintype "passive"))
      (node (ref "Q10") (pin "E") (pinfunction "E_E") (pintype "passive"))
      (node (ref "R39") (pin "1") (pinfunction "1_1") (pintype "passive"))
    )
    (net (code "46") (name "Net-(D23-PadA)") (class "Default")
      (node (ref "D23") (pin "A") (pinfunction "A_A") (pintype "passive"))
      (node (ref "Q11") (pin "E") (pinfunction "E_E") (pintype "passive"))
      (node (ref "R38") (pin "1") (pinfunction "1_1") (pintype "passive"))
    )
    (net (code "47") (name "Net-(D24-Pad2)") (class "Default")
      (node (ref "D24") (pin "2") (pinfunction "2_2") (pintype "passive"))
      (node (ref "D25") (pin "C") (pinfunction "C_C") (pintype "passive"))
      (node (ref "R25") (pin "1") (pinfunction "1_1") (pintype "passive"))
      (node (ref "R26") (pin "1") (pinfunction "1_1") (pintype "passive"))
    )
    (net (code "48") (name "Net-(D26-PadA)") (class "Default")
      (node (ref "D26") (pin "A") (pinfunction "A_A") (pintype "passive"))
      (node (ref "Q12") (pin "E") (pinfunction "E_E") (pintype "passive"))
      (node (ref "R37") (pin "1") (pinfunction "1_1") (pintype "passive"))
    )
    (net (code "49") (name "Net-(D30-Pad2)") (class "Default")
      (node (ref "D30") (pin "2") (pinfunction "2_2") (pintype "passive"))
      (node (ref "D31") (pin "C") (pinfunction "C_C") (pintype "passive"))
      (node (ref "R31") (pin "1") (pinfunction "1_1") (pintype "passive"))
      (node (ref "R32") (pin "1") (pinfunction "1_1") (pintype "passive"))
    )
    (net (code "50") (name "Net-(LED2-PadA)") (class "Default")
      (node (ref "LED2") (pin "A") (pinfunction "A_A") (pintype "passive"))
      (node (ref "R5") (pin "2") (pinfunction "2_2") (pintype "passive"))
    )
    (net (code "51") (name "Net-(LED3-PadA)") (class "Default")
      (node (ref "LED3") (pin "A") (pinfunction "A_A") (pintype "passive"))
      (node (ref "R8") (pin "2") (pinfunction "2_2") (pintype "passive"))
    )
    (net (code "52") (name "Net-(LED4-PadA)") (class "Default")
      (node (ref "LED4") (pin "A") (pinfunction "A_A") (pintype "passive"))
      (node (ref "R11") (pin "2") (pinfunction "2_2") (pintype "passive"))
    )
    (net (code "53") (name "Net-(LED5-PadA)") (class "Default")
      (node (ref "LED5") (pin "A") (pinfunction "A_A") (pintype "passive"))
      (node (ref "R14") (pin "2") (pinfunction "2_2") (pintype "passive"))
    )
    (net (code "54") (name "Net-(LED6-PadA)") (class "Default")
      (node (ref "LED6") (pin "A") (pinfunction "A_A") (pintype "passive"))
      (node (ref "R17") (pin "2") (pinfunction "2_2") (pintype "passive"))
    )
    (net (code "55") (name "Net-(LED7-PadA)") (class "Default")
      (node (ref "LED7") (pin "A") (pinfunction "A_A") (pintype "passive"))
      (node (ref "R20") (pin "2") (pinfunction "2_2") (pintype "passive"))
    )
    (net (code "56") (name "Net-(LED9-PadA)") (class "Default")
      (node (ref "LED9") (pin "A") (pinfunction "A_A") (pintype "passive"))
      (node (ref "R26") (pin "2") (pinfunction "2_2") (pintype "passive"))
    )
    (net (code "57") (name "Net-(LED11-PadA)") (class "Default")
      (node (ref "LED11") (pin "A") (pinfunction "A_A") (pintype "passive"))
      (node (ref "R32") (pin "2") (pinfunction "2_2") (pintype "passive"))
    )
    (net (code "58") (name "Net-(OK3A-A)") (class "Default")
      (node (ref "OK3") (pin "1") (pinfunction "A_1") (pintype "passive"))
      (node (ref "R6") (pin "2") (pinfunction "2_2") (pintype "passive"))
    )
    (net (code "59") (name "Net-(OK3A-EMIT)") (class "Default")
      (node (ref "OK3") (pin "15") (pinfunction "EMIT_15") (pintype "passive"))
      (node (ref "R18") (pin "1") (pinfunction "1_1") (pintype "passive"))
    )
    (net (code "60") (name "Net-(OK3B-A)") (class "Default")
      (node (ref "OK3") (pin "3") (pinfunction "A_3") (pintype "passive"))
      (node (ref "R9") (pin "2") (pinfunction "2_2") (pintype "passive"))
    )
    (net (code "61") (name "Net-(OK3B-EMIT)") (class "Default")
      (node (ref "OK3") (pin "13") (pinfunction "EMIT_13") (pintype "passive"))
      (node (ref "R21") (pin "1") (pinfunction "1_1") (pintype "passive"))
    )
    (net (code "62") (name "Net-(OK3C-A)") (class "Default")
      (node (ref "OK3") (pin "5") (pinfunction "A_5") (pintype "passive"))
      (node (ref "R12") (pin "2") (pinfunction "2_2") (pintype "passive"))
    )
    (net (code "63") (name "Net-(OK3C-EMIT)") (class "Default")
      (node (ref "OK3") (pin "11") (pinfunction "EMIT_11") (pintype "passive"))
      (node (ref "R27") (pin "1") (pinfunction "1_1") (pintype "passive"))
    )
    (net (code "64") (name "Net-(OK3D-A)") (class "Default")
      (node (ref "OK3") (pin "7") (pinfunction "A_7") (pintype "passive"))
      (node (ref "R15") (pin "2") (pinfunction "2_2") (pintype "passive"))
    )
    (net (code "65") (name "Net-(OK3D-EMIT)") (class "Default")
      (node (ref "OK3") (pin "9") (pinfunction "EMIT_9") (pintype "passive"))
      (node (ref "R30") (pin "1") (pinfunction "1_1") (pintype "passive"))
    )
    (net (code "66") (name "Net-(OK5A-A)") (class "Default")
      (node (ref "OK5") (pin "1") (pinfunction "A_1") (pintype "passive"))
      (node (ref "R41") (pin "2") (pinfunction "2_2") (pintype "passive"))
    )
    (net (code "67") (name "Net-(OK5A-EMIT)") (class "Default")
      (node (ref "OK5") (pin "15") (pinfunction "EMIT_15") (pintype "passive"))
      (node (ref "R45") (pin "1") (pinfunction "1_1") (pintype "passive"))
    )
    (net (code "68") (name "Net-(OK5B-A)") (class "Default")
      (node (ref "OK5") (pin "3") (pinfunction "A_3") (pintype "passive"))
      (node (ref "R42") (pin "2") (pinfunction "2_2") (pintype "passive"))
    )
    (net (code "69") (name "Net-(OK5B-EMIT)") (class "Default")
      (node (ref "OK5") (pin "13") (pinfunction "EMIT_13") (pintype "passive"))
      (node (ref "R46") (pin "1") (pinfunction "1_1") (pintype "passive"))
    )
    (net (code "70") (name "Net-(OK5C-A)") (class "Default")
      (node (ref "OK5") (pin "5") (pinfunction "A_5") (pintype "passive"))
      (node (ref "R43") (pin "2") (pinfunction "2_2") (pintype "passive"))
    )
    (net (code "71") (name "Net-(OK5C-EMIT)") (class "Default")
      (node (ref "OK5") (pin "11") (pinfunction "EMIT_11") (pintype "passive"))
      (node (ref "R47") (pin "1") (pinfunction "1_1") (pintype "passive"))
    )
    (net (code "72") (name "Net-(OK5D-A)") (class "Default")
      (node (ref "OK5") (pin "7") (pinfunction "A_7") (pintype "passive"))
      (node (ref "R44") (pin "2") (pinfunction "2_2") (pintype "passive"))
    )
    (net (code "73") (name "Net-(OK5D-EMIT)") (class "Default")
      (node (ref "OK5") (pin "9") (pinfunction "EMIT_9") (pintype "passive"))
      (node (ref "R48") (pin "1") (pinfunction "1_1") (pintype "passive"))
    )
    (net (code "74") (name "Net-(Q1-PadB)") (class "Default")
      (node (ref "Q1") (pin "B") (pinfunction "B_B") (pintype "passive"))
      (node (ref "R18") (pin "2") (pinfunction "2_2") (pintype "passive"))
    )
    (net (code "75") (name "Net-(Q2-PadB)") (class "Default")
      (node (ref "Q2") (pin "B") (pinfunction "B_B") (pintype "passive"))
      (node (ref "R21") (pin "2") (pinfunction "2_2") (pintype "passive"))
    )
    (net (code "76") (name "Net-(Q3-PadB)") (class "Default")
      (node (ref "Q3") (pin "B") (pinfunction "B_B") (pintype "passive"))
      (node (ref "R27") (pin "2") (pinfunction "2_2") (pintype "passive"))
    )
    (net (code "77") (name "Net-(Q4-PadB)") (class "Default")
      (node (ref "Q4") (pin "B") (pinfunction "B_B") (pintype "passive"))
      (node (ref "R30") (pin "2") (pinfunction "2_2") (pintype "passive"))
    )
    (net (code "78") (name "Net-(Q9-PadB)") (class "Default")
      (node (ref "Q9") (pin "B") (pinfunction "B_B") (pintype "passive"))
      (node (ref "R45") (pin "2") (pinfunction "2_2") (pintype "passive"))
    )
    (net (code "79") (name "Net-(Q10-PadB)") (class "Default")
      (node (ref "Q10") (pin "B") (pinfunction "B_B") (pintype "passive"))
      (node (ref "R46") (pin "2") (pinfunction "2_2") (pintype "passive"))
    )
    (net (code "80") (name "Net-(Q11-PadB)") (class "Default")
      (node (ref "Q11") (pin "B") (pinfunction "B_B") (pintype "passive"))
      (node (ref "R47") (pin "2") (pinfunction "2_2") (pintype "passive"))
    )
    (net (code "81") (name "Net-(Q12-PadB)") (class "Default")
      (node (ref "Q12") (pin "B") (pinfunction "B_B") (pintype "passive"))
      (node (ref "R48") (pin "2") (pinfunction "2_2") (pintype "passive"))
    )
    (net (code "82") (name "Net-(R34-Pad2)") (class "Default")
      (node (ref "R34") (pin "2") (pinfunction "2_2") (pintype "passive"))
      (node (ref "X1") (pin "1") (pinfunction "1_1") (pintype "passive"))
    )
    (net (code "83") (name "Net-(R35-Pad2)") (class "Default")
      (node (ref "R35") (pin "2") (pinfunction "2_2") (pintype "passive"))
      (node (ref "X4") (pin "1") (pinfunction "1_1") (pintype "passive"))
    )
    (net (code "84") (name "Net-(R40-Pad2)") (class "Default")
      (node (ref "R40") (pin "2") (pinfunction "2_2") (pintype "passive"))
      (node (ref "X2") (pin "1") (pinfunction "1_1") (pintype "passive"))
    )
    (net (code "85") (name "Net-(X1B-1)") (class "Default")
      (node (ref "R38") (pin "2") (pinfunction "2_2") (pintype "passive"))
      (node (ref "X1") (pin "2") (pinfunction "1_2") (pintype "passive"))
    )
    (net (code "86") (name "Net-(X1C-1)") (class "Default")
      (node (ref "R37") (pin "2") (pinfunction "2_2") (pintype "passive"))
      (node (ref "X1") (pin "3") (pinfunction "1_3") (pintype "passive"))
    )
    (net (code "87") (name "Net-(X2B-1)") (class "Default")
      (node (ref "R39") (pin "2") (pinfunction "2_2") (pintype "passive"))
      (node (ref "X2") (pin "2") (pinfunction "1_2") (pintype "passive"))
    )
    (net (code "88") (name "Net-(X4B-1)") (class "Default")
      (node (ref "R36") (pin "2") (pinfunction "2_2") (pintype "passive"))
      (node (ref "X4") (pin "2") (pinfunction "1_2") (pintype "passive"))
    )
    (net (code "89") (name "Net-(X4C-1)") (class "Default")
      (node (ref "R33") (pin "2") (pinfunction "2_2") (pintype "passive"))
      (node (ref "X4") (pin "3") (pinfunction "1_3") (pintype "passive"))
    )
    (net (code "90") (name "Net-(X6C-1)") (class "Default")
      (node (ref "D25") (pin "A") (pinfunction "A_A") (pintype "passive"))
      (node (ref "X6") (pin "3") (pinfunction "1_3") (pintype "passive"))
    )
    (net (code "91") (name "PB0") (class "Default")
      (node (ref "R6") (pin "1") (pinfunction "1_1") (pintype "passive"))
      (node (ref "U1") (pin "P1_27") (pinfunction "PB0_P1_27") (pintype "bidirectional"))
    )
    (net (code "92") (name "PB1") (class "Default")
      (node (ref "R9") (pin "1") (pinfunction "1_1") (pintype "passive"))
      (node (ref "U1") (pin "P1_28") (pinfunction "PB1_P1_28") (pintype "bidirectional"))
    )
    (net (code "93") (name "PB2") (class "Default")
      (node (ref "R12") (pin "1") (pinfunction "1_1") (pintype "passive"))
      (node (ref "U1") (pin "P1_29") (pinfunction "PB2_P1_29") (pintype "bidirectional"))
    )
    (net (code "94") (name "PB3") (class "Default")
      (node (ref "R15") (pin "1") (pinfunction "1_1") (pintype "passive"))
      (node (ref "U1") (pin "P2_11") (pinfunction "PB3_P2_11") (pintype "bidirectional"))
    )
    (net (code "95") (name "PB4") (class "Default")
      (node (ref "R41") (pin "1") (pinfunction "1_1") (pintype "passive"))
      (node (ref "U1") (pin "P2_10") (pinfunction "PB4_P2_10") (pintype "bidirectional"))
    )
    (net (code "96") (name "PB5") (class "Default")
      (node (ref "R42") (pin "1") (pinfunction "1_1") (pintype "passive"))
      (node (ref "U1") (pin "P2_9") (pinfunction "PB5_P2_9") (pintype "bidirectional"))
    )
    (net (code "97") (name "PB6") (class "Default")
      (node (ref "R43") (pin "1") (pinfunction "1_1") (pintype "passive"))
      (node (ref "U1") (pin "P2_8") (pinfunction "PB6_P2_8") (pintype "bidirectional"))
    )
    (net (code "98") (name "PB7") (class "Default")
      (node (ref "R44") (pin "1") (pinfunction "1_1") (pintype "passive"))
      (node (ref "U1") (pin "P2_7") (pinfunction "PB7_P2_7") (pintype "bidirectional"))
    )
    (net (code "99") (name "PC0") (class "Default")
      (node (ref "OK2") (pin "16") (pinfunction "COL_16") (pintype "passive"))
      (node (ref "R1") (pin "1") (pinfunction "1_1") (pintype "passive"))
      (node (ref "U1") (pin "P1_11") (pinfunction "PC0_P1_11") (pintype "bidirectional"))
    )
    (net (code "100") (name "PC1") (class "Default")
      (node (ref "OK2") (pin "14") (pinfunction "COL_14") (pintype "passive"))
      (node (ref "R2") (pin "1") (pinfunction "1_1") (pintype "passive"))
      (node (ref "U1") (pin "P1_12") (pinfunction "PC1_P1_12") (pintype "bidirectional"))
    )
    (net (code "101") (name "PC2") (class "Default")
      (node (ref "OK2") (pin "12") (pinfunction "COL_12") (pintype "passive"))
      (node (ref "R3") (pin "1") (pinfunction "1_1") (pintype "passive"))
      (node (ref "U1") (pin "P1_13") (pinfunction "PC2_P1_13") (pintype "bidirectional"))
    )
    (net (code "102") (name "PC3") (class "Default")
      (node (ref "OK2") (pin "10") (pinfunction "COL_10") (pintype "passive"))
      (node (ref "R22") (pin "1") (pinfunction "1_1") (pintype "passive"))
      (node (ref "U1") (pin "P1_14") (pinfunction "PC3_P1_14") (pintype "bidirectional"))
    )
    (net (code "103") (name "PC4") (class "Default")
      (node (ref "OK1") (pin "16") (pinfunction "COL_16") (pintype "passive"))
      (node (ref "R23") (pin "1") (pinfunction "1_1") (pintype "passive"))
      (node (ref "U1") (pin "P1_25") (pinfunction "PC4_P1_25") (pintype "bidirectional"))
    )
    (net (code "104") (name "PC5") (class "Default")
      (node (ref "OK1") (pin "14") (pinfunction "COL_14") (pintype "passive"))
      (node (ref "R24") (pin "1") (pinfunction "1_1") (pintype "passive"))
      (node (ref "U1") (pin "P1_26") (pinfunction "PC5_P1_26") (pintype "bidirectional"))
    )
    (net (code "105") (name "PC6") (class "Default")
      (node (ref "OK1") (pin "12") (pinfunction "COL_12") (pintype "passive"))
      (node (ref "R28") (pin "1") (pinfunction "1_1") (pintype "passive"))
      (node (ref "U1") (pin "P2_29") (pinfunction "PC6_P2_29") (pintype "bidirectional"))
    )
    (net (code "106") (name "PC7") (class "Default")
      (node (ref "OK1") (pin "10") (pinfunction "COL_10") (pintype "passive"))
      (node (ref "R29") (pin "1") (pinfunction "1_1") (pintype "passive"))
      (node (ref "U1") (pin "P2_28") (pinfunction "PC7_P2_28") (pintype "bidirectional"))
    )
    (net (code "107") (name "SEL0") (class "Default")
      (node (ref "SV1") (pin "1") (pinfunction "1_1") (pintype "passive"))
      (node (ref "U1") (pin "P1_4") (pinfunction "PC13_P1_4") (pintype "bidirectional"))
    )
    (net (code "108") (name "SEL1") (class "Default")
      (node (ref "SV1") (pin "3") (pinfunction "3_3") (pintype "passive"))
      (node (ref "U1") (pin "P1_5") (pinfunction "PC14_P1_5") (pintype "bidirectional"))
    )
    (net (code "109") (name "SEL2") (class "Default")
      (node (ref "SV1") (pin "5") (pinfunction "5_5") (pintype "passive"))
      (node (ref "U1") (pin "P1_6") (pinfunction "PC15_P1_6") (pintype "bidirectional"))
    )
    (net (code "110") (name "SPI1_MISO") (class "Default")
      (node (ref "SV1") (pin "4") (pinfunction "4_4") (pintype "passive"))
      (node (ref "U1") (pin "P1_23") (pinfunction "PA6_P1_23") (pintype "bidirectional"))
    )
    (net (code "111") (name "SPI1_MOSI") (class "Default")
      (node (ref "SV1") (pin "2") (pinfunction "2_2") (pintype "passive"))
      (node (ref "U1") (pin "P1_24") (pinfunction "PA7_P1_24") (pintype "bidirectional"))
    )
    (net (code "112") (name "SPI1_SCK") (class "Default")
      (node (ref "SV1") (pin "6") (pinfunction "6_6") (pintype "passive"))
      (node (ref "U1") (pin "P1_22") (pinfunction "PA5_P1_22") (pintype "bidirectional"))
    )
    (net (code "113") (name "USART1_RX") (class "Default")
      (node (ref "SV2") (pin "2") (pinfunction "2_2") (pintype "passive"))
      (node (ref "U1") (pin "P2_23") (pinfunction "PA10_P2_23") (pintype "bidirectional"))
    )
    (net (code "114") (name "USART1_TX") (class "Default")
      (node (ref "SV2") (pin "1") (pinfunction "1_1") (pintype "passive"))
      (node (ref "U1") (pin "P2_24") (pinfunction "PA9_P2_24") (pintype "bidirectional"))
    )
    (net (code "115") (name "USART2_RX") (class "Default")
      (node (ref "IC3") (pin "1") (pinfunction "R_1") (pintype "input"))
      (node (ref "U1") (pin "P1_18") (pinfunction "PA3_P1_18") (pintype "bidirectional"))
    )
    (net (code "116") (name "USART2_TX") (class "Default")
      (node (ref "IC1") (pin "4") (pinfunction "D_4") (pintype "input"))
      (node (ref "U1") (pin "P1_17") (pinfunction "PA2_P1_17") (pintype "bidirectional"))
    )
    (net (code "117") (name "unconnected-(IC1-R-Pad1)") (class "Default")
      (node (ref "IC1") (pin "1") (pinfunction "R_1") (pintype "input"))
    )
    (net (code "118") (name "unconnected-(IC3-D-Pad4)") (class "Default")
      (node (ref "IC3") (pin "4") (pinfunction "D_4") (pintype "input"))
    )
    (net (code "119") (name "unconnected-(SV1-Pad7)") (class "Default")
      (node (ref "SV1") (pin "7") (pinfunction "7_7") (pintype "passive"))
    )
    (net (code "120") (name "unconnected-(SV1-Pad8)") (class "Default")
      (node (ref "SV1") (pin "8") (pinfunction "8_8") (pintype "passive"))
    )
    (net (code "121") (name "unconnected-(U1-BOOT0-PadP2_6)") (class "Default")
      (node (ref "U1") (pin "P2_6") (pinfunction "BOOT0_P2_6") (pintype "bidirectional"))
    )
    (net (code "122") (name "unconnected-(U1-NRST-PadP1_10)") (class "Default")
      (node (ref "U1") (pin "P1_10") (pinfunction "NRST_P1_10") (pintype "bidirectional"))
    )
    (net (code "123") (name "unconnected-(U1-PA0-PadP1_15)") (class "Default")
      (node (ref "U1") (pin "P1_15") (pinfunction "PA0_P1_15") (pintype "bidirectional"))
    )
    (net (code "124") (name "unconnected-(U1-PA1-PadP1_16)") (class "Default")
      (node (ref "U1") (pin "P1_16") (pinfunction "PA1_P1_16") (pintype "bidirectional"))
    )
    (net (code "125") (name "unconnected-(U1-PA4-PadP1_21)") (class "Default")
      (node (ref "U1") (pin "P1_21") (pinfunction "PA4_P1_21") (pintype "bidirectional"))
    )
    (net (code "126") (name "unconnected-(U1-PA8-PadP2_25)") (class "Default")
      (node (ref "U1") (pin "P2_25") (pinfunction "PA8_P2_25") (pintype "bidirectional"))
    )
    (net (code "127") (name "unconnected-(U1-PA11-PadP2_22)") (class "Default")
      (node (ref "U1") (pin "P2_22") (pinfunction "PA11_P2_22") (pintype "bidirectional"))
    )
    (net (code "128") (name "unconnected-(U1-PA12-PadP2_21)") (class "Default")
      (node (ref "U1") (pin "P2_21") (pinfunction "PA12_P2_21") (pintype "bidirectional"))
    )
    (net (code "129") (name "unconnected-(U1-PA13-PadP2_20)") (class "Default")
      (node (ref "U1") (pin "P2_20") (pinfunction "PA13_P2_20") (pintype "bidirectional"))
    )
    (net (code "130") (name "unconnected-(U1-PA14-PadP2_17)") (class "Default")
      (node (ref "U1") (pin "P2_17") (pinfunction "PA14_P2_17") (pintype "bidirectional"))
    )
    (net (code "131") (name "unconnected-(U1-PA15-PadP2_16)") (class "Default")
      (node (ref "U1") (pin "P2_16") (pinfunction "PA15_P2_16") (pintype "bidirectional"))
    )
    (net (code "132") (name "unconnected-(U1-PB8-PadP2_4)") (class "Default")
      (node (ref "U1") (pin "P2_4") (pinfunction "PB8_P2_4") (pintype "bidirectional"))
    )
    (net (code "133") (name "unconnected-(U1-PB9-PadP2_3)") (class "Default")
      (node (ref "U1") (pin "P2_3") (pinfunction "PB9_P2_3") (pintype "bidirectional"))
    )
    (net (code "134") (name "unconnected-(U1-PB10-PadP1_30)") (class "Default")
      (node (ref "U1") (pin "P1_30") (pinfunction "PB10_P1_30") (pintype "bidirectional"))
    )
    (net (code "135") (name "unconnected-(U1-PB11-PadP1_31)") (class "Default")
      (node (ref "U1") (pin "P1_31") (pinfunction "PB11_P1_31") (pintype "bidirectional"))
    )
    (net (code "136") (name "unconnected-(U1-PB12-PadP1_32)") (class "Default")
      (node (ref "U1") (pin "P1_32") (pinfunction "PB12_P1_32") (pintype "bidirectional"))
    )
    (net (code "137") (name "unconnected-(U1-PB13-PadP2_32)") (class "Default")
      (node (ref "U1") (pin "P2_32") (pinfunction "PB13_P2_32") (pintype "bidirectional"))
    )
    (net (code "138") (name "unconnected-(U1-PB14-PadP2_31)") (class "Default")
      (node (ref "U1") (pin "P2_31") (pinfunction "PB14_P2_31") (pintype "bidirectional"))
    )
    (net (code "139") (name "unconnected-(U1-PB15-PadP2_30)") (class "Default")
      (node (ref "U1") (pin "P2_30") (pinfunction "PB15_P2_30") (pintype "bidirectional"))
    )
    (net (code "140") (name "unconnected-(U1-PC8-PadP2_27)") (class "Default")
      (node (ref "U1") (pin "P2_27") (pinfunction "PC8_P2_27") (pintype "bidirectional"))
    )
    (net (code "141") (name "unconnected-(U1-PC9-PadP2_26)") (class "Default")
      (node (ref "U1") (pin "P2_26") (pinfunction "PC9_P2_26") (pintype "bidirectional"))
    )
    (net (code "142") (name "unconnected-(U1-PC10-PadP2_15)") (class "Default")
      (node (ref "U1") (pin "P2_15") (pinfunction "PC10_P2_15") (pintype "bidirectional"))
    )
    (net (code "143") (name "unconnected-(U1-PC11-PadP2_14)") (class "Default")
      (node (ref "U1") (pin "P2_14") (pinfunction "PC11_P2_14") (pintype "bidirectional"))
    )
    (net (code "144") (name "unconnected-(U1-PC12-PadP2_13)") (class "Default")
      (node (ref "U1") (pin "P2_13") (pinfunction "PC12_P2_13") (pintype "bidirectional"))
    )
    (net (code "145") (name "unconnected-(U1-PD2-PadP2_12)") (class "Default")
      (node (ref "U1") (pin "P2_12") (pinfunction "PD2_P2_12") (pintype "bidirectional"))
    )
    (net (code "146") (name "unconnected-(U1-PH0-PadP1_7)") (class "Default")
      (node (ref "U1") (pin "P1_7") (pinfunction "PH0_P1_7") (pintype "bidirectional"))
    )
    (net (code "147") (name "unconnected-(U1-PH1-PadP1_8)") (class "Default")
      (node (ref "U1") (pin "P1_8") (pinfunction "PH1_P1_8") (pintype "bidirectional"))
    )
  )
)
